# S7CAS-PLEIADES-CARTE-MERE_P07_MOT.net
KiCad netlist of a schematic drawn in Altium Designer
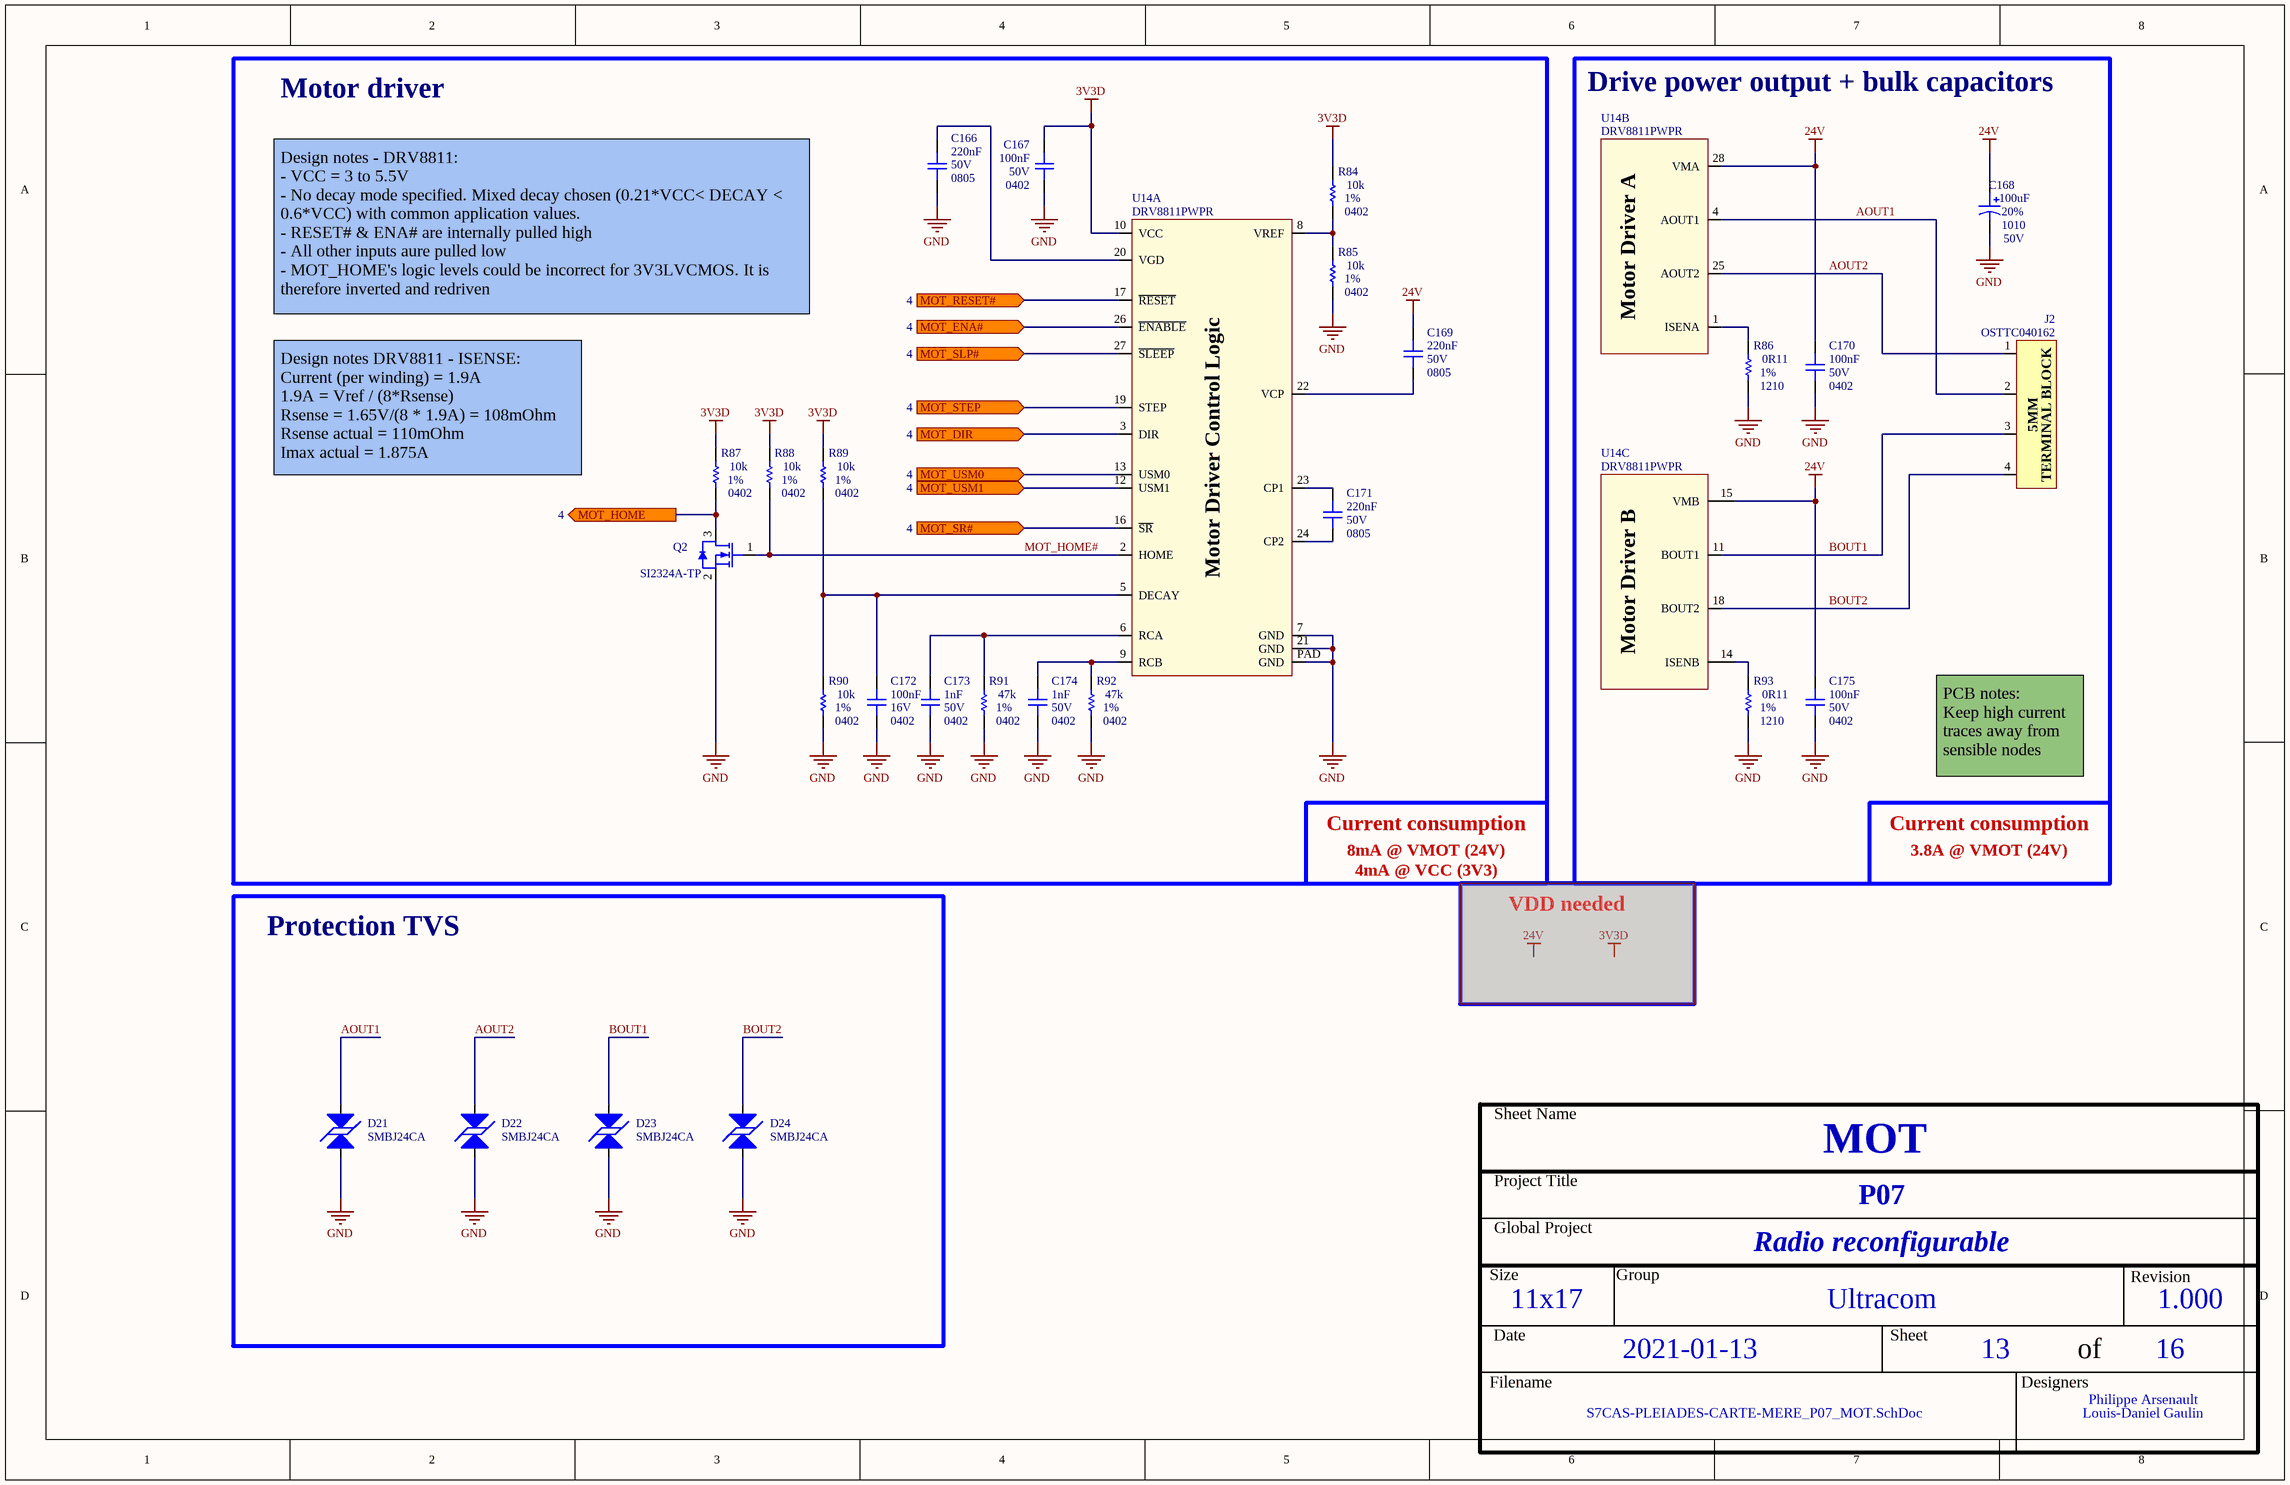
[diagram p0: S7CAS-PLEIADES-CARTE-MERE_P07_MOT.SchDoc]

(export (version "E")
  (design (tool "Eeschema 10.0.6"))
  (components
    (comp (ref "C166")
      (value "220nF")
      (footprint "CAP_0805")
      (description "CAP - 0805")
      (fields
        (field (name "MFG PART NUMBER") "CL21B224KBFNNNE")
        (field (name "VOLTAGE") "50V")
        (field (name "PACKAGE") "0805")
        (field (name "CREATEDBY") "Jonathan Bouchard")
      )
      (libsource (lib "S7CAS_LIB2021") (part "CAP - 0805"))
    )
    (comp (ref "C167")
      (value "100nF")
      (footprint "CAP_0402")
      (description "CAP - 0402")
      (fields
        (field (name "VOLTAGE") "50V")
        (field (name "PACKAGE") "0402")
        (field (name "CREATEDBY") "Jonathan Bouchard")
      )
      (libsource (lib "S7CAS_LIB2021") (part "CAP - 0402"))
    )
    (comp (ref "C168")
      (value "100uF")
      (footprint "CAP_ALU_1010_vishay")
      (description "CAP - ALU 100uF 20% 50V - 1010")
      (fields
        (field (name "MFG") "Vishay Dale")
        (field (name "MFG PART NUMBER") "MAL215099101E3")
        (field (name "VOLTAGE") "50V")
        (field (name "PACKAGE") "1010")
        (field (name "PRECISION") "20%")
        (field (name "CREATEDBY") "Jonathan Bouchard")
      )
      (libsource (lib "S7CAS_LIB2021") (part "CAP_ALU_MAL215099101E3"))
    )
    (comp (ref "C169")
      (value "220nF")
      (footprint "CAP_0805")
      (description "CAP - 0805")
      (fields
        (field (name "MFG PART NUMBER") "CL21B224KBFNNNE")
        (field (name "VOLTAGE") "50V")
        (field (name "PACKAGE") "0805")
        (field (name "CREATEDBY") "Jonathan Bouchard")
      )
      (libsource (lib "S7CAS_LIB2021") (part "CAP - 0805"))
    )
    (comp (ref "C170")
      (value "100nF")
      (footprint "CAP_0402")
      (description "CAP - 0402")
      (fields
        (field (name "MFG") "C1005X7R1H102K050BA")
        (field (name "VOLTAGE") "50V")
        (field (name "PACKAGE") "0402")
        (field (name "CREATEDBY") "Jonathan Bouchard")
      )
      (libsource (lib "S7CAS_LIB2021") (part "CAP - 0402"))
    )
    (comp (ref "C171")
      (value "220nF")
      (footprint "CAP_0805")
      (description "CAP - 0805")
      (fields
        (field (name "MFG PART NUMBER") "CL21B224KBFNNNE")
        (field (name "VOLTAGE") "50V")
        (field (name "PACKAGE") "0805")
        (field (name "CREATEDBY") "Jonathan Bouchard")
      )
      (libsource (lib "S7CAS_LIB2021") (part "CAP - 0805"))
    )
    (comp (ref "C172")
      (value "100nF")
      (footprint "CAP_0402")
      (description "CAP - 0402")
      (fields
        (field (name "MFG PART NUMBER") "CL05B104KO5NNNC")
        (field (name "VOLTAGE") "16V")
        (field (name "PACKAGE") "0402")
        (field (name "CREATEDBY") "Jonathan Bouchard")
      )
      (libsource (lib "S7CAS_LIB2021") (part "CAP - 0402"))
    )
    (comp (ref "C173")
      (value "1nF")
      (footprint "CAP_0402")
      (description "CAP - 0402")
      (fields
        (field (name "MFG") "C1005X7R1H102K050BA")
        (field (name "VOLTAGE") "50V")
        (field (name "PACKAGE") "0402")
        (field (name "CREATEDBY") "Jonathan Bouchard")
      )
      (libsource (lib "S7CAS_LIB2021") (part "CAP - 0402"))
    )
    (comp (ref "C174")
      (value "1nF")
      (footprint "CAP_0402")
      (description "CAP - 0402")
      (fields
        (field (name "MFG") "C1005X7R1H102K050BA")
        (field (name "VOLTAGE") "50V")
        (field (name "PACKAGE") "0402")
        (field (name "CREATEDBY") "Jonathan Bouchard")
      )
      (libsource (lib "S7CAS_LIB2021") (part "CAP - 0402"))
    )
    (comp (ref "C175")
      (value "100nF")
      (footprint "CAP_0402")
      (description "CAP - 0402")
      (fields
        (field (name "MFG") "C1005X7R1H102K050BA")
        (field (name "VOLTAGE") "50V")
        (field (name "PACKAGE") "0402")
        (field (name "CREATEDBY") "Jonathan Bouchard")
      )
      (libsource (lib "S7CAS_LIB2021") (part "CAP - 0402"))
    )
    (comp (ref "D21")
      (value "SMBJ24CA")
      (footprint "TVS_PWR_SMBJ36CA")
      (description "TVS - 24V 26.7V 600W - DO214AA")
      (fields
        (field (name "CREATEDBY/DATE") "Arnaud Samson - 06/07/18")
        (field (name "VERIFIEDBY") "Jonathan Bouchard - 2018-07-13")
      )
      (libsource (lib "S7CAS_LIB2021") (part "TVS_PWR_SMBJ24CA"))
    )
    (comp (ref "D22")
      (value "SMBJ24CA")
      (footprint "TVS_PWR_SMBJ36CA")
      (description "TVS - 24V 26.7V 600W - DO214AA")
      (fields
        (field (name "CREATEDBY/DATE") "Arnaud Samson - 06/07/18")
        (field (name "VERIFIEDBY") "Jonathan Bouchard - 2018-07-13")
      )
      (libsource (lib "S7CAS_LIB2021") (part "TVS_PWR_SMBJ24CA"))
    )
    (comp (ref "D23")
      (value "SMBJ24CA")
      (footprint "TVS_PWR_SMBJ36CA")
      (description "TVS - 24V 26.7V 600W - DO214AA")
      (fields
        (field (name "CREATEDBY/DATE") "Arnaud Samson - 06/07/18")
        (field (name "VERIFIEDBY") "Jonathan Bouchard - 2018-07-13")
      )
      (libsource (lib "S7CAS_LIB2021") (part "TVS_PWR_SMBJ24CA"))
    )
    (comp (ref "D24")
      (value "SMBJ24CA")
      (footprint "TVS_PWR_SMBJ36CA")
      (description "TVS - 24V 26.7V 600W - DO214AA")
      (fields
        (field (name "CREATEDBY/DATE") "Arnaud Samson - 06/07/18")
        (field (name "VERIFIEDBY") "Jonathan Bouchard - 2018-07-13")
      )
      (libsource (lib "S7CAS_LIB2021") (part "TVS_PWR_SMBJ24CA"))
    )
    (comp (ref "J2")
      (value "OSTTC040162")
      (footprint "CONN_TERMINAL_OSTTA040161")
      (description "CONN -  TERMINAL BLOCK 4POS 5MM - TH")
      (fields (field (name "MFG") "On Shore Technology Inc.") (field (name "CREATEDBY") "Jonathan Bouchard"))
      (libsource (lib "S7CAS_LIB2021") (part "CONN_TERMINAL_OSTTC040162"))
    )
    (comp (ref "Q2")
      (value "SI2324A-TP")
      (footprint "TRX_NMOS_SI324A-TP")
      (description "TRX - MOSFET N-CH 100V 2A - SOT-23")
      (fields (field (name "CREATEDBY/DATE") "*") (field (name "VERIFIEDBY") "*"))
      (libsource (lib "S7CAS_P07") (part "TRX_NMOS_SI2324A-TP"))
    )
    (comp (ref "R84")
      (value "10k")
      (footprint "RES_0402")
      (description "RES - 0402")
      (fields
        (field (name "VOLTAGE") "50V")
        (field (name "POWER") "1/16W")
        (field (name "PACKAGE") "0402")
        (field (name "PRECISION") "1%")
        (field (name "CREATEDBY") "Jonathan Bouchard")
      )
      (libsource (lib "S7CAS_LIB2021") (part "RES - 0402"))
    )
    (comp (ref "R85")
      (value "10k")
      (footprint "RES_0402")
      (description "RES - 0402")
      (fields
        (field (name "VOLTAGE") "50V")
        (field (name "POWER") "1/16W")
        (field (name "PACKAGE") "0402")
        (field (name "PRECISION") "1%")
        (field (name "CREATEDBY") "Jonathan Bouchard")
      )
      (libsource (lib "S7CAS_LIB2021") (part "RES - 0402"))
    )
    (comp (ref "R86")
      (value "0R11")
      (footprint "RES_1210")
      (description "RES - 1210")
      (fields
        (field (name "POWER") "1/16W")
        (field (name "PACKAGE") "1210")
        (field (name "PRECISION") "1%")
        (field (name "CREATEDBY") "Jonathan Bouchard")
      )
      (libsource (lib "S7CAS_LIB2021") (part "RES - 1210"))
    )
    (comp (ref "R87")
      (value "10k")
      (footprint "RES_0402")
      (description "RES - 0402")
      (fields
        (field (name "VOLTAGE") "50V")
        (field (name "POWER") "1/16W")
        (field (name "PACKAGE") "0402")
        (field (name "PRECISION") "1%")
        (field (name "CREATEDBY") "Jonathan Bouchard")
      )
      (libsource (lib "S7CAS_LIB2021") (part "RES - 0402"))
    )
    (comp (ref "R88")
      (value "10k")
      (footprint "RES_0402")
      (description "RES - 0402")
      (fields
        (field (name "VOLTAGE") "50V")
        (field (name "POWER") "1/16W")
        (field (name "PACKAGE") "0402")
        (field (name "PRECISION") "1%")
        (field (name "CREATEDBY") "Jonathan Bouchard")
      )
      (libsource (lib "S7CAS_LIB2021") (part "RES - 0402"))
    )
    (comp (ref "R89")
      (value "10k")
      (footprint "RES_0402")
      (description "RES - 0402")
      (fields
        (field (name "VOLTAGE") "50V")
        (field (name "POWER") "1/16W")
        (field (name "PACKAGE") "0402")
        (field (name "PRECISION") "1%")
        (field (name "CREATEDBY") "Jonathan Bouchard")
      )
      (libsource (lib "S7CAS_LIB2021") (part "RES - 0402"))
    )
    (comp (ref "R90")
      (value "10k")
      (footprint "RES_0402")
      (description "RES - 0402")
      (fields
        (field (name "VOLTAGE") "50V")
        (field (name "POWER") "1/16W")
        (field (name "PACKAGE") "0402")
        (field (name "PRECISION") "1%")
        (field (name "CREATEDBY") "Jonathan Bouchard")
      )
      (libsource (lib "S7CAS_LIB2021") (part "RES - 0402"))
    )
    (comp (ref "R91")
      (value "47k")
      (footprint "RES_0402")
      (description "RES - 0402")
      (fields
        (field (name "VOLTAGE") "50V")
        (field (name "POWER") "1/16W")
        (field (name "PACKAGE") "0402")
        (field (name "PRECISION") "1%")
        (field (name "CREATEDBY") "Jonathan Bouchard")
      )
      (libsource (lib "S7CAS_LIB2021") (part "RES - 0402"))
    )
    (comp (ref "R92")
      (value "47k")
      (footprint "RES_0402")
      (description "RES - 0402")
      (fields
        (field (name "VOLTAGE") "50V")
        (field (name "POWER") "1/16W")
        (field (name "PACKAGE") "0402")
        (field (name "PRECISION") "1%")
        (field (name "CREATEDBY") "Jonathan Bouchard")
      )
      (libsource (lib "S7CAS_LIB2021") (part "RES - 0402"))
    )
    (comp (ref "R93")
      (value "0R11")
      (footprint "RES_1210")
      (description "RES - 1210")
      (fields
        (field (name "POWER") "1/16W")
        (field (name "PACKAGE") "1210")
        (field (name "PRECISION") "1%")
        (field (name "CREATEDBY") "Jonathan Bouchard")
      )
      (libsource (lib "S7CAS_LIB2021") (part "RES - 1210"))
    )
    (comp (ref "U14")
      (value "DRV8811PWPR")
      (footprint "POW_MOTOR_DRV8811PWPR")
      (description "POW - STEPPER MOTOR DRIVER - SOP-28")
      (fields
        (field (name "VOLTAGE") "3 V ~ 5.5 V / 8 V ~ 38 V")
        (field (name "MFG") "Texas Instrument")
        (field (name "CREATEDBY") "Jonathan Bouchard")
      )
      (libsource (lib "S7CAS_LIB2021") (part "POW_MOTOR_DRV8811PWPR"))
    )
  )
  (nets
    (net (code "1") (name "/AOUT1") (class "Default")
      (node (ref "D21") (pin "1") (pinfunction "1_1") (pintype "passive"))
      (node (ref "J2") (pin "2") (pinfunction "2_2") (pintype "passive"))
      (node (ref "U14") (pin "4") (pinfunction "AOUT1_4") (pintype "passive"))
    )
    (net (code "2") (name "/AOUT2") (class "Default")
      (node (ref "D22") (pin "1") (pinfunction "1_1") (pintype "passive"))
      (node (ref "J2") (pin "1") (pinfunction "1_1") (pintype "passive"))
      (node (ref "U14") (pin "25") (pinfunction "AOUT2_25") (pintype "passive"))
    )
    (net (code "3") (name "/BOUT1") (class "Default")
      (node (ref "D23") (pin "1") (pinfunction "1_1") (pintype "passive"))
      (node (ref "J2") (pin "3") (pinfunction "3_3") (pintype "passive"))
      (node (ref "U14") (pin "11") (pinfunction "BOUT1_11") (pintype "passive"))
    )
    (net (code "4") (name "/BOUT2") (class "Default")
      (node (ref "D24") (pin "1") (pinfunction "1_1") (pintype "passive"))
      (node (ref "J2") (pin "4") (pinfunction "4_4") (pintype "passive"))
      (node (ref "U14") (pin "18") (pinfunction "BOUT2_18") (pintype "passive"))
    )
    (net (code "5") (name "/MOT_DIR") (class "Default")
      (node (ref "U14") (pin "3") (pinfunction "DIR_3") (pintype "passive"))
    )
    (net (code "6") (name "/MOT_ENA#") (class "Default")
      (node (ref "U14") (pin "26") (pinfunction "~{ENABLE}_26") (pintype "passive"))
    )
    (net (code "7") (name "/MOT_HOME") (class "Default")
      (node (ref "Q2") (pin "3") (pinfunction "D_3") (pintype "passive"))
      (node (ref "R87") (pin "1") (pinfunction "1_1") (pintype "passive"))
    )
    (net (code "8") (name "/MOT_HOME#") (class "Default")
      (node (ref "Q2") (pin "1") (pinfunction "G_1") (pintype "passive"))
      (node (ref "R88") (pin "1") (pinfunction "1_1") (pintype "passive"))
      (node (ref "U14") (pin "2") (pinfunction "HOME_2") (pintype "passive"))
    )
    (net (code "9") (name "/MOT_RESET#") (class "Default")
      (node (ref "U14") (pin "17") (pinfunction "~{RESET}_17") (pintype "passive"))
    )
    (net (code "10") (name "/MOT_SLP#") (class "Default")
      (node (ref "U14") (pin "27") (pinfunction "~{SLEEP}_27") (pintype "passive"))
    )
    (net (code "11") (name "/MOT_SR#") (class "Default")
      (node (ref "U14") (pin "16") (pinfunction "~{SR}_16") (pintype "passive"))
    )
    (net (code "12") (name "/MOT_STEP") (class "Default")
      (node (ref "U14") (pin "19") (pinfunction "STEP_19") (pintype "passive"))
    )
    (net (code "13") (name "/MOT_USM0") (class "Default")
      (node (ref "U14") (pin "13") (pinfunction "USM0_13") (pintype "passive"))
    )
    (net (code "14") (name "/MOT_USM1") (class "Default")
      (node (ref "U14") (pin "12") (pinfunction "USM1_12") (pintype "passive"))
    )
    (net (code "15") (name "3V3D") (class "Default")
      (node (ref "C167") (pin "2") (pinfunction "2_2") (pintype "passive"))
      (node (ref "R84") (pin "2") (pinfunction "2_2") (pintype "passive"))
      (node (ref "R87") (pin "2") (pinfunction "2_2") (pintype "passive"))
      (node (ref "R88") (pin "2") (pinfunction "2_2") (pintype "passive"))
      (node (ref "R89") (pin "2") (pinfunction "2_2") (pintype "passive"))
      (node (ref "U14") (pin "10") (pinfunction "VCC_10") (pintype "passive"))
    )
    (net (code "16") (name "24V") (class "Default")
      (node (ref "C168") (pin "1") (pinfunction "1_1") (pintype "passive"))
      (node (ref "C169") (pin "2") (pinfunction "2_2") (pintype "passive"))
      (node (ref "C170") (pin "2") (pinfunction "2_2") (pintype "passive"))
      (node (ref "C175") (pin "2") (pinfunction "2_2") (pintype "passive"))
      (node (ref "U14") (pin "15") (pinfunction "VMB_15") (pintype "passive"))
      (node (ref "U14") (pin "28") (pinfunction "VMA_28") (pintype "passive"))
    )
    (net (code "17") (name "GND") (class "Default")
      (node (ref "C166") (pin "2") (pinfunction "2_2") (pintype "passive"))
      (node (ref "C167") (pin "1") (pinfunction "1_1") (pintype "passive"))
      (node (ref "C168") (pin "2") (pinfunction "2_2") (pintype "passive"))
      (node (ref "C170") (pin "1") (pinfunction "1_1") (pintype "passive"))
      (node (ref "C172") (pin "1") (pinfunction "1_1") (pintype "passive"))
      (node (ref "C173") (pin "1") (pinfunction "1_1") (pintype "passive"))
      (node (ref "C174") (pin "1") (pinfunction "1_1") (pintype "passive"))
      (node (ref "C175") (pin "1") (pinfunction "1_1") (pintype "passive"))
      (node (ref "D21") (pin "2") (pinfunction "2_2") (pintype "passive"))
      (node (ref "D22") (pin "2") (pinfunction "2_2") (pintype "passive"))
      (node (ref "D23") (pin "2") (pinfunction "2_2") (pintype "passive"))
      (node (ref "D24") (pin "2") (pinfunction "2_2") (pintype "passive"))
      (node (ref "Q2") (pin "2") (pinfunction "S_2") (pintype "passive"))
      (node (ref "R85") (pin "1") (pinfunction "1_1") (pintype "passive"))
      (node (ref "R86") (pin "1") (pinfunction "1_1") (pintype "passive"))
      (node (ref "R90") (pin "1") (pinfunction "1_1") (pintype "passive"))
      (node (ref "R91") (pin "1") (pinfunction "1_1") (pintype "passive"))
      (node (ref "R92") (pin "1") (pinfunction "1_1") (pintype "passive"))
      (node (ref "R93") (pin "1") (pinfunction "1_1") (pintype "passive"))
      (node (ref "U14") (pin "21") (pinfunction "GND_21") (pintype "passive"))
      (node (ref "U14") (pin "7") (pinfunction "GND_7") (pintype "passive"))
      (node (ref "U14") (pin "PAD") (pinfunction "GND_PAD") (pintype "passive"))
    )
    (net (code "18") (name "Net-(U14A-CP1)") (class "Default")
      (node (ref "C171") (pin "2") (pinfunction "2_2") (pintype "passive"))
      (node (ref "U14") (pin "23") (pinfunction "CP1_23") (pintype "passive"))
    )
    (net (code "19") (name "Net-(U14A-CP2)") (class "Default")
      (node (ref "C171") (pin "1") (pinfunction "1_1") (pintype "passive"))
      (node (ref "U14") (pin "24") (pinfunction "CP2_24") (pintype "passive"))
    )
    (net (code "20") (name "Net-(U14A-DECAY)") (class "Default")
      (node (ref "C172") (pin "2") (pinfunction "2_2") (pintype "passive"))
      (node (ref "R89") (pin "1") (pinfunction "1_1") (pintype "passive"))
      (node (ref "R90") (pin "2") (pinfunction "2_2") (pintype "passive"))
      (node (ref "U14") (pin "5") (pinfunction "DECAY_5") (pintype "passive"))
    )
    (net (code "21") (name "Net-(U14A-RCA)") (class "Default")
      (node (ref "C173") (pin "2") (pinfunction "2_2") (pintype "passive"))
      (node (ref "R91") (pin "2") (pinfunction "2_2") (pintype "passive"))
      (node (ref "U14") (pin "6") (pinfunction "RCA_6") (pintype "passive"))
    )
    (net (code "22") (name "Net-(U14A-RCB)") (class "Default")
      (node (ref "C174") (pin "2") (pinfunction "2_2") (pintype "passive"))
      (node (ref "R92") (pin "2") (pinfunction "2_2") (pintype "passive"))
      (node (ref "U14") (pin "9") (pinfunction "RCB_9") (pintype "passive"))
    )
    (net (code "23") (name "Net-(U14A-VCP)") (class "Default")
      (node (ref "C169") (pin "1") (pinfunction "1_1") (pintype "passive"))
      (node (ref "U14") (pin "22") (pinfunction "VCP_22") (pintype "passive"))
    )
    (net (code "24") (name "Net-(U14A-VGD)") (class "Default")
      (node (ref "C166") (pin "1") (pinfunction "1_1") (pintype "passive"))
      (node (ref "U14") (pin "20") (pinfunction "VGD_20") (pintype "passive"))
    )
    (net (code "25") (name "Net-(U14A-VREF)") (class "Default")
      (node (ref "R84") (pin "1") (pinfunction "1_1") (pintype "passive"))
      (node (ref "R85") (pin "2") (pinfunction "2_2") (pintype "passive"))
      (node (ref "U14") (pin "8") (pinfunction "VREF_8") (pintype "passive"))
    )
    (net (code "26") (name "Net-(U14B-ISENA)") (class "Default")
      (node (ref "R86") (pin "2") (pinfunction "2_2") (pintype "passive"))
      (node (ref "U14") (pin "1") (pinfunction "ISENA_1") (pintype "passive"))
    )
    (net (code "27") (name "Net-(U14C-ISENB)") (class "Default")
      (node (ref "R93") (pin "2") (pinfunction "2_2") (pintype "passive"))
      (node (ref "U14") (pin "14") (pinfunction "ISENB_14") (pintype "passive"))
    )
  )
)
